# Mux_side_B.net
KiCad netlist of a schematic drawn in Altium Designer
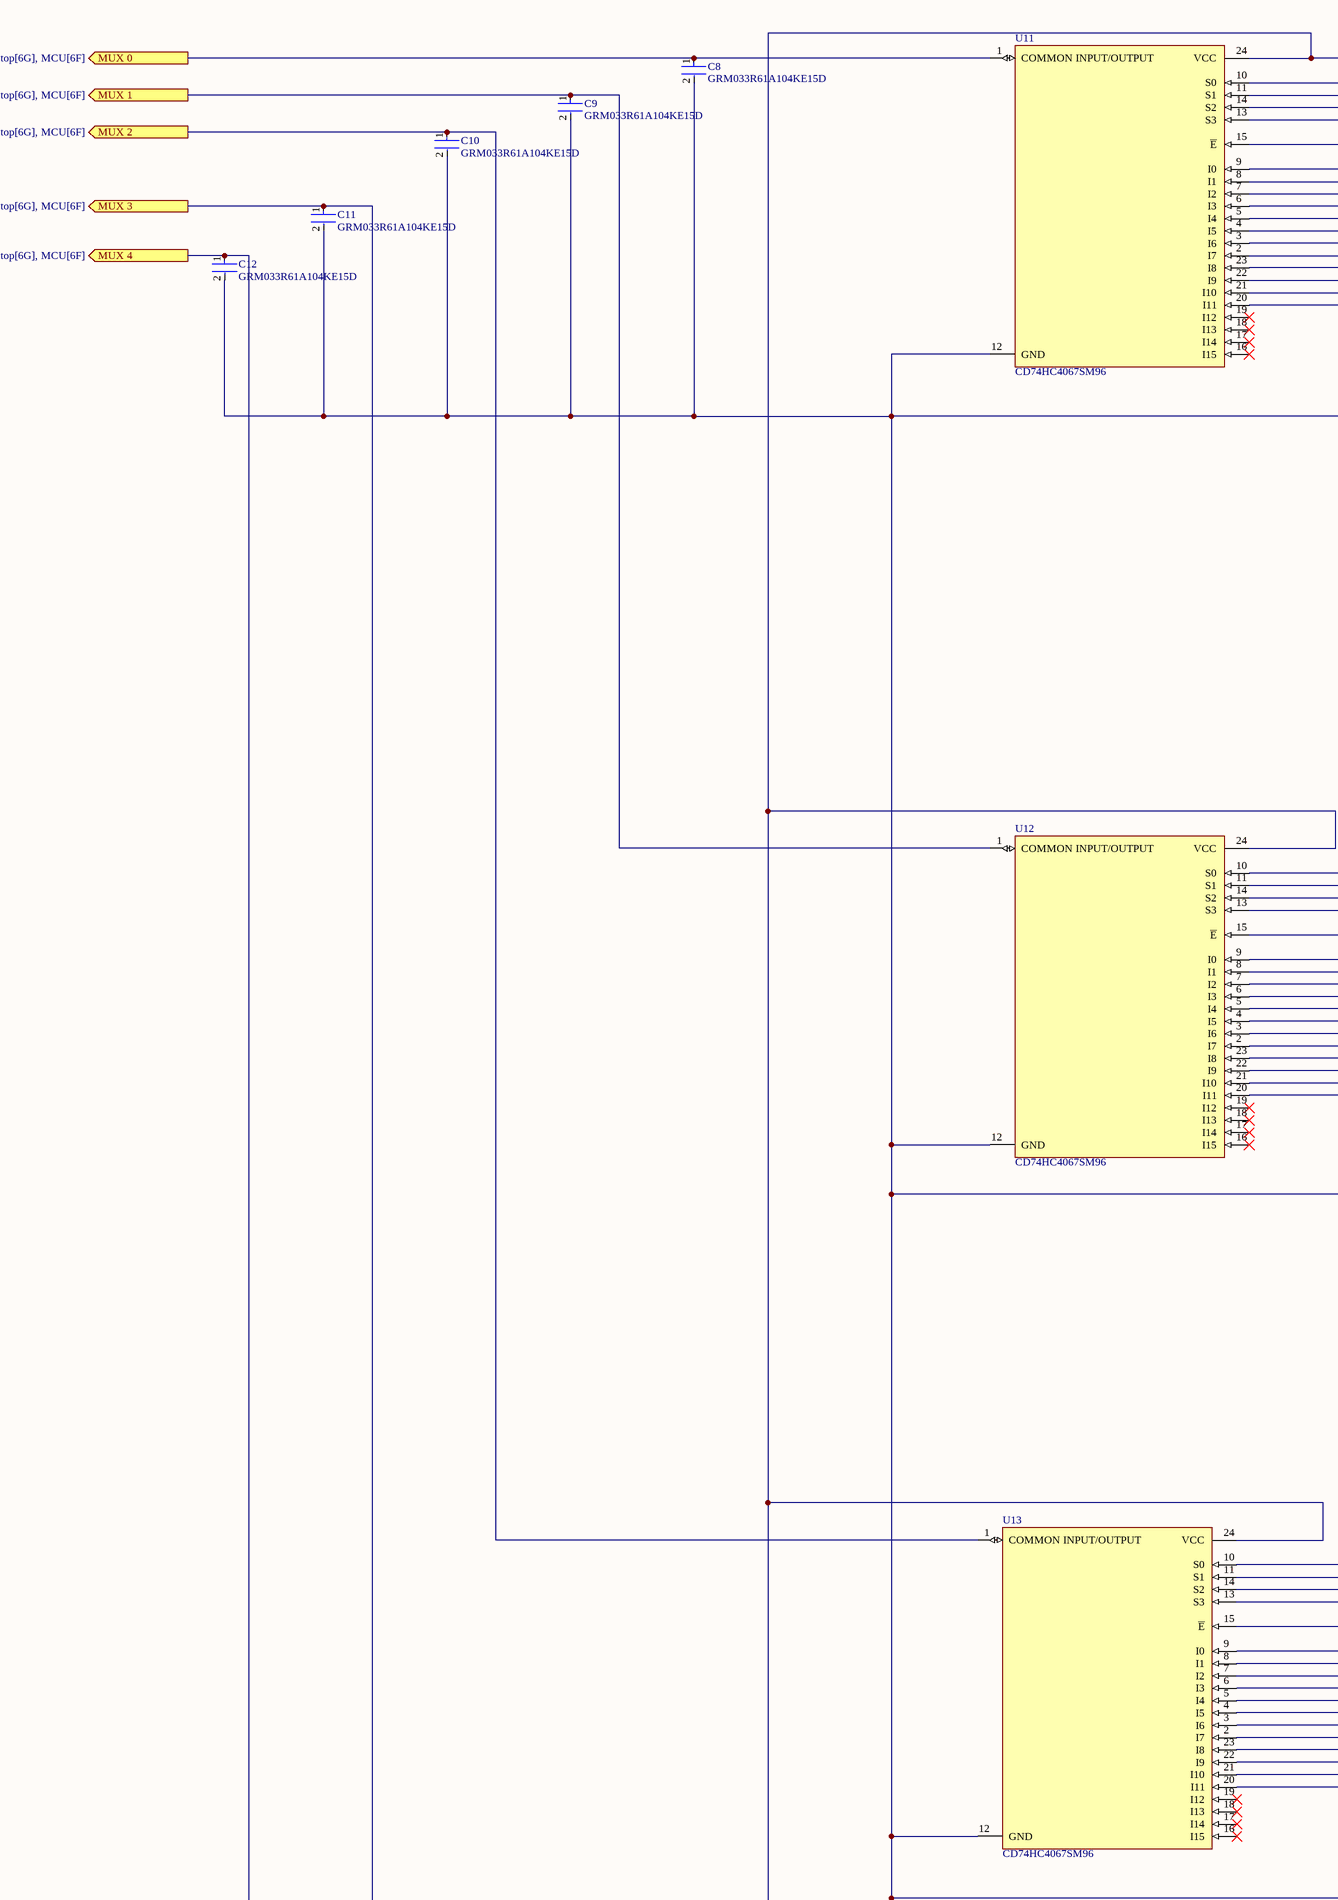
[diagram p0: Mux side B (5-8).SchDoc, top left]
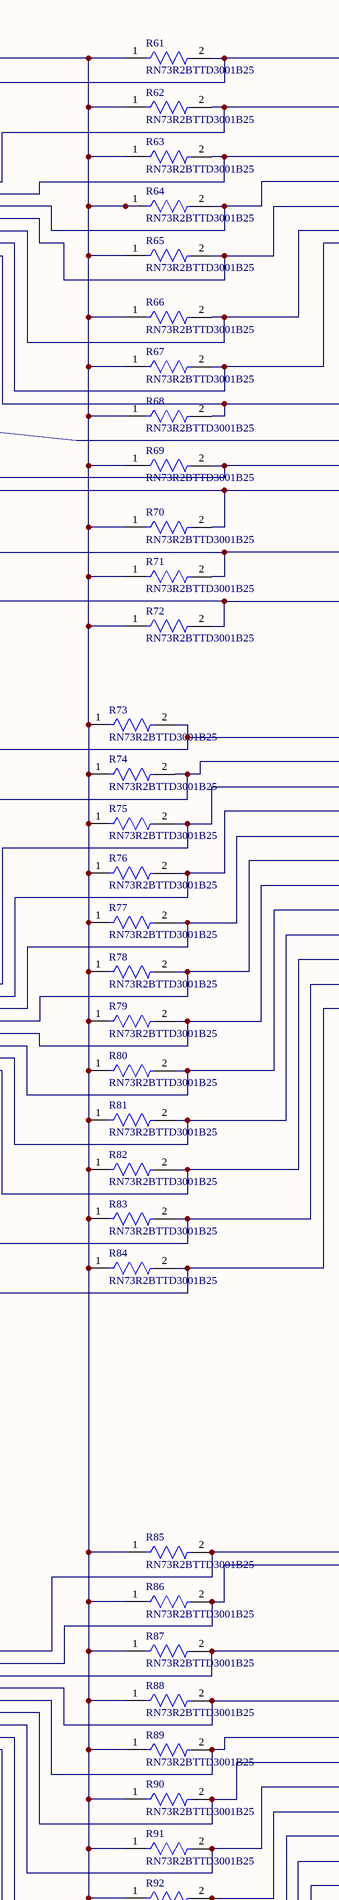
[diagram p1: Mux side B (5-8).SchDoc, top middle]
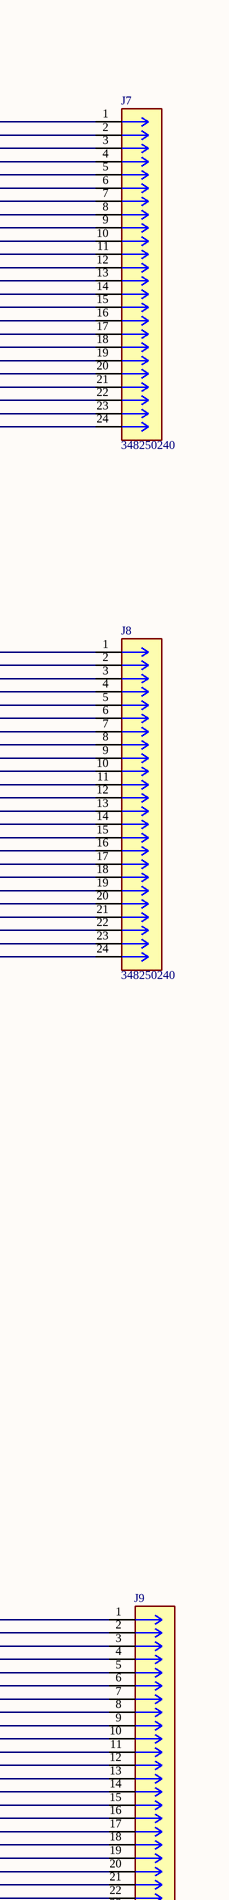
[diagram p2: Mux side B (5-8).SchDoc, top right]
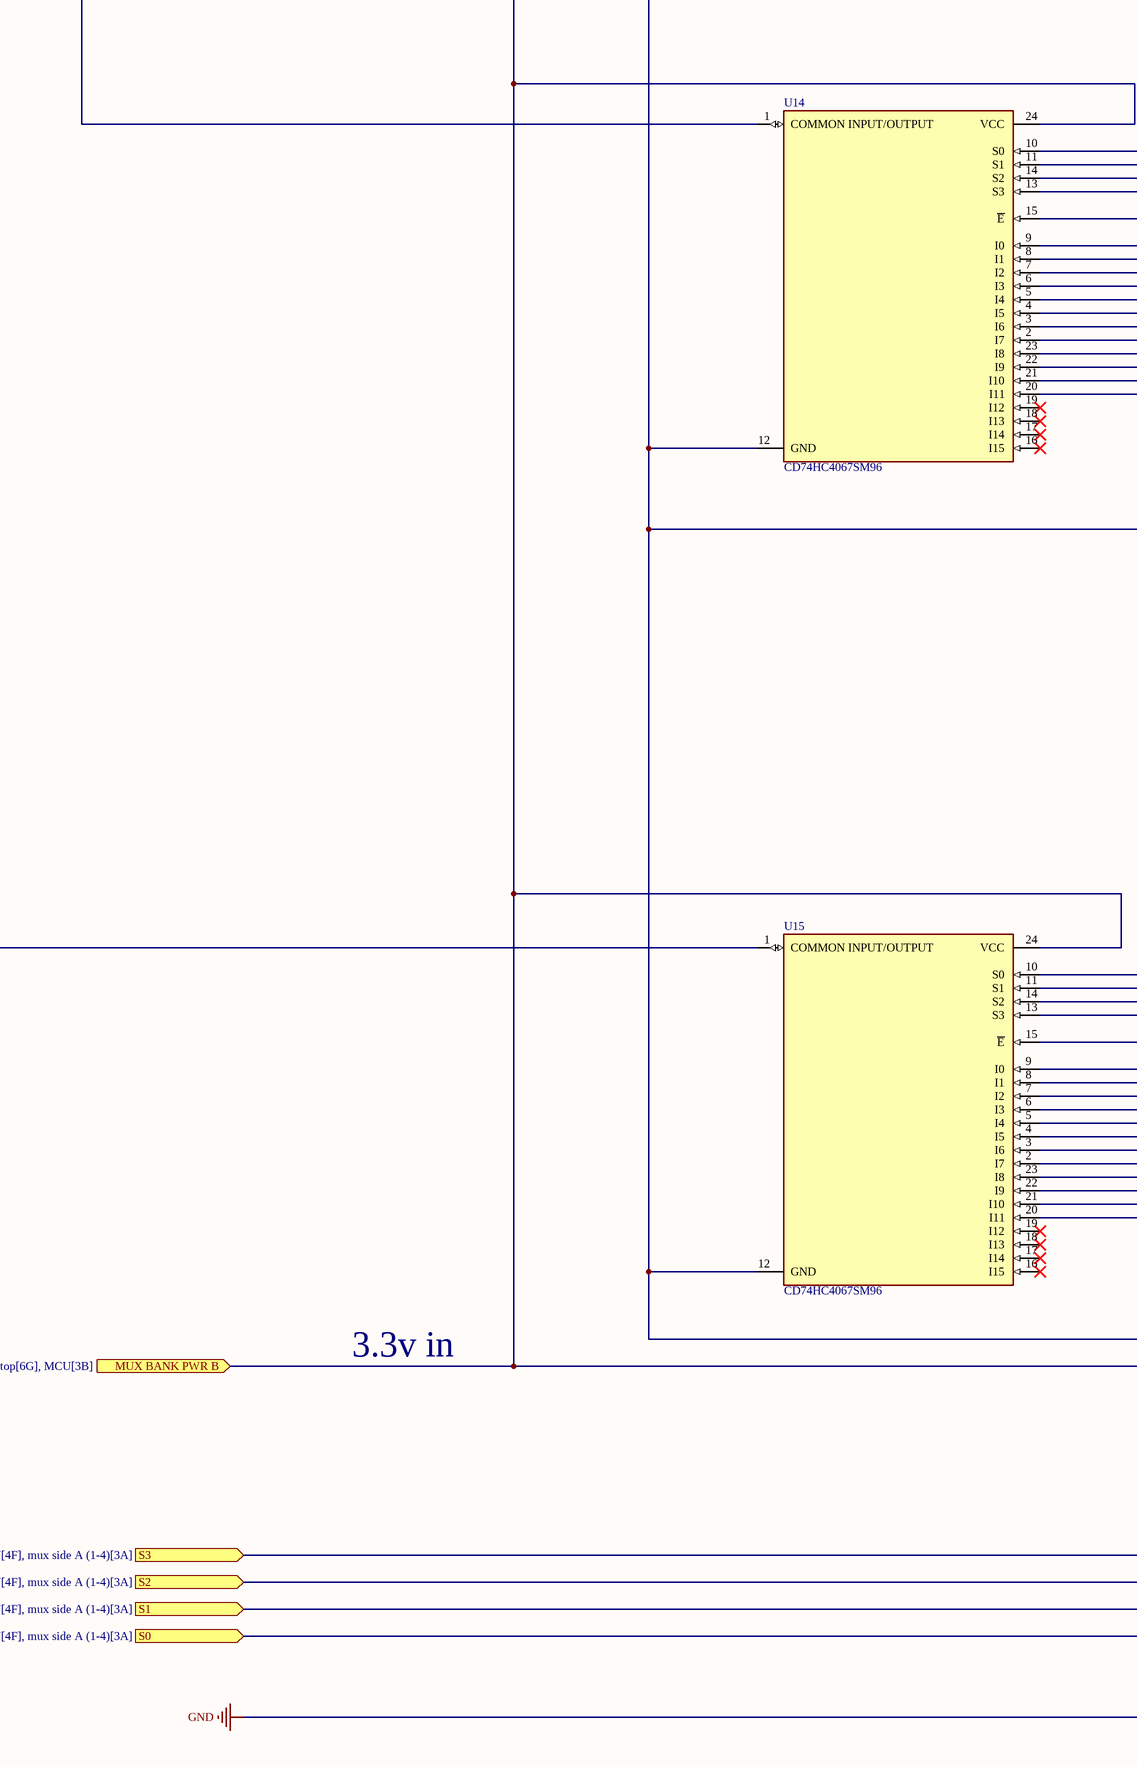
[diagram p3: Mux side B (5-8).SchDoc, bottom left]
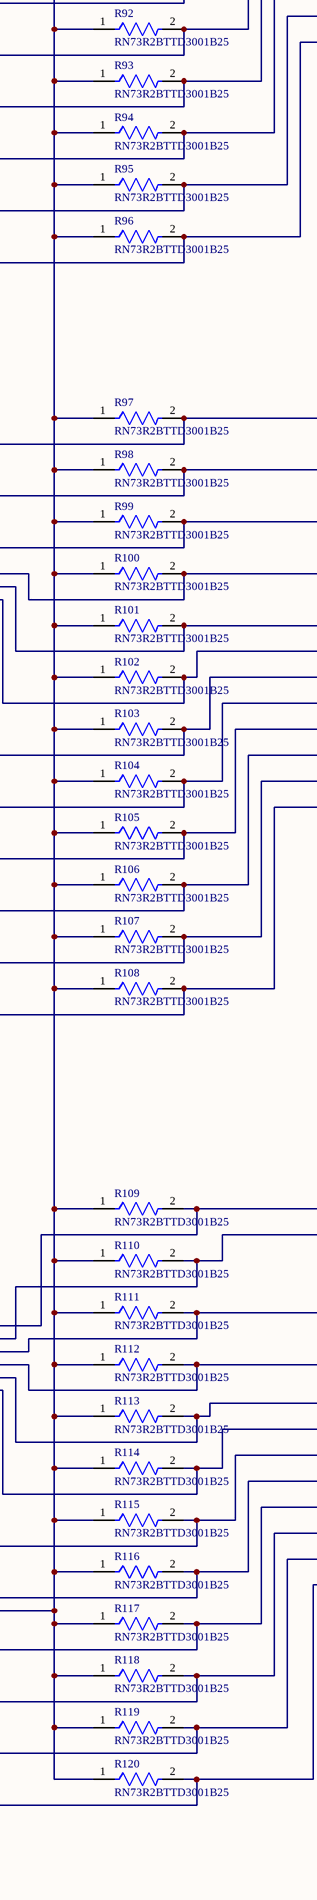
[diagram p4: Mux side B (5-8).SchDoc, bottom middle]
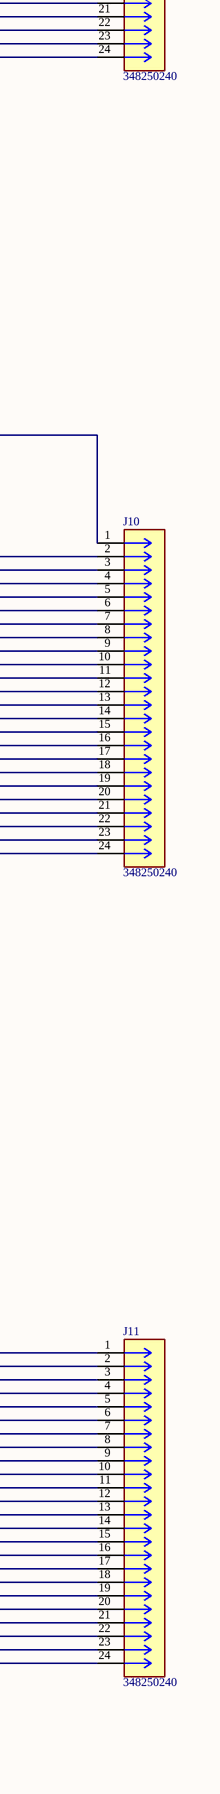
[diagram p5: Mux side B (5-8).SchDoc, bottom right]

(export (version "E")
  (design (tool "Eeschema 10.0.6"))
  (components
    (comp (ref "C8")
      (value "GRM033R61A104KE15D")
      (footprint "FP-GRM033-0_03-IPC_C")
      (description "Chip Multilayer Ceramic Capacitors for General Purpose, 0201, 0.10uF, X5R, 15%, 10%, 10V")
      (fields (field (name "TOLERANCE") "10%") (field (name "VOLTAGE") "10V"))
      (libsource (lib "Altium Content Vault") (part "b4654b650e69147ec39a6b967a45e02"))
    )
    (comp (ref "C9")
      (value "GRM033R61A104KE15D")
      (footprint "FP-GRM033-0_03-IPC_C")
      (description "Chip Multilayer Ceramic Capacitors for General Purpose, 0201, 0.10uF, X5R, 15%, 10%, 10V")
      (fields (field (name "TOLERANCE") "10%") (field (name "VOLTAGE") "10V"))
      (libsource (lib "Altium Content Vault") (part "b4654b650e69147ec39a6b967a45e02"))
    )
    (comp (ref "C10")
      (value "GRM033R61A104KE15D")
      (footprint "FP-GRM033-0_03-IPC_C")
      (description "Chip Multilayer Ceramic Capacitors for General Purpose, 0201, 0.10uF, X5R, 15%, 10%, 10V")
      (fields (field (name "TOLERANCE") "10%") (field (name "VOLTAGE") "10V"))
      (libsource (lib "Altium Content Vault") (part "b4654b650e69147ec39a6b967a45e02"))
    )
    (comp (ref "C11")
      (value "GRM033R61A104KE15D")
      (footprint "FP-GRM033-0_03-IPC_C")
      (description "Chip Multilayer Ceramic Capacitors for General Purpose, 0201, 0.10uF, X5R, 15%, 10%, 10V")
      (fields (field (name "TOLERANCE") "10%") (field (name "VOLTAGE") "10V"))
      (libsource (lib "Altium Content Vault") (part "b4654b650e69147ec39a6b967a45e02"))
    )
    (comp (ref "C12")
      (value "GRM033R61A104KE15D")
      (footprint "FP-GRM033-0_03-IPC_C")
      (description "Chip Multilayer Ceramic Capacitors for General Purpose, 0201, 0.10uF, X5R, 15%, 10%, 10V")
      (fields (field (name "TOLERANCE") "10%") (field (name "VOLTAGE") "10V"))
      (libsource (lib "Altium Content Vault") (part "b4654b650e69147ec39a6b967a45e02"))
    )
    (comp (ref "J7")
      (value "348250240")
      (footprint "CONN_SD-34825-001_24_MOL")
      (libsource (lib "348250240") (part "348250240"))
    )
    (comp (ref "J8")
      (value "348250240")
      (footprint "CONN_SD-34825-001_24_MOL")
      (libsource (lib "348250240") (part "348250240"))
    )
    (comp (ref "J9")
      (value "348250240")
      (footprint "CONN_SD-34825-001_24_MOL")
      (libsource (lib "348250240") (part "348250240"))
    )
    (comp (ref "J10")
      (value "348250240")
      (footprint "CONN_SD-34825-001_24_MOL")
      (libsource (lib "348250240") (part "348250240"))
    )
    (comp (ref "J11")
      (value "348250240")
      (footprint "CONN_SD-34825-001_24_MOL")
      (libsource (lib "348250240") (part "348250240"))
    )
    (comp (ref "R61")
      (value "RN73R2BTTD3001B25")
      (footprint "FP-RN73R2B-IPC_A")
      (description "3kΩ ±0.1% 0.25W, 1/4W Chip Resistor 1206 (3216 Metric) Moisture Resistant Thin Film")
      (libsource (lib "Altium Content Vault") (part "1029c3af85768c4190bb7ad29bc67b5"))
    )
    (comp (ref "R62")
      (value "RN73R2BTTD3001B25")
      (footprint "FP-RN73R2B-IPC_A")
      (description "3kΩ ±0.1% 0.25W, 1/4W Chip Resistor 1206 (3216 Metric) Moisture Resistant Thin Film")
      (libsource (lib "Altium Content Vault") (part "1029c3af85768c4190bb7ad29bc67b5"))
    )
    (comp (ref "R63")
      (value "RN73R2BTTD3001B25")
      (footprint "FP-RN73R2B-IPC_A")
      (description "3kΩ ±0.1% 0.25W, 1/4W Chip Resistor 1206 (3216 Metric) Moisture Resistant Thin Film")
      (libsource (lib "Altium Content Vault") (part "1029c3af85768c4190bb7ad29bc67b5"))
    )
    (comp (ref "R64")
      (value "RN73R2BTTD3001B25")
      (footprint "FP-RN73R2B-IPC_A")
      (description "3kΩ ±0.1% 0.25W, 1/4W Chip Resistor 1206 (3216 Metric) Moisture Resistant Thin Film")
      (libsource (lib "Altium Content Vault") (part "1029c3af85768c4190bb7ad29bc67b5"))
    )
    (comp (ref "R65")
      (value "RN73R2BTTD3001B25")
      (footprint "FP-RN73R2B-IPC_A")
      (description "3kΩ ±0.1% 0.25W, 1/4W Chip Resistor 1206 (3216 Metric) Moisture Resistant Thin Film")
      (libsource (lib "Altium Content Vault") (part "1029c3af85768c4190bb7ad29bc67b5"))
    )
    (comp (ref "R66")
      (value "RN73R2BTTD3001B25")
      (footprint "FP-RN73R2B-IPC_A")
      (description "3kΩ ±0.1% 0.25W, 1/4W Chip Resistor 1206 (3216 Metric) Moisture Resistant Thin Film")
      (libsource (lib "Altium Content Vault") (part "1029c3af85768c4190bb7ad29bc67b5"))
    )
    (comp (ref "R67")
      (value "RN73R2BTTD3001B25")
      (footprint "FP-RN73R2B-IPC_A")
      (description "3kΩ ±0.1% 0.25W, 1/4W Chip Resistor 1206 (3216 Metric) Moisture Resistant Thin Film")
      (libsource (lib "Altium Content Vault") (part "1029c3af85768c4190bb7ad29bc67b5"))
    )
    (comp (ref "R68")
      (value "RN73R2BTTD3001B25")
      (footprint "FP-RN73R2B-IPC_A")
      (description "3kΩ ±0.1% 0.25W, 1/4W Chip Resistor 1206 (3216 Metric) Moisture Resistant Thin Film")
      (libsource (lib "Altium Content Vault") (part "1029c3af85768c4190bb7ad29bc67b5"))
    )
    (comp (ref "R69")
      (value "RN73R2BTTD3001B25")
      (footprint "FP-RN73R2B-IPC_A")
      (description "3kΩ ±0.1% 0.25W, 1/4W Chip Resistor 1206 (3216 Metric) Moisture Resistant Thin Film")
      (libsource (lib "Altium Content Vault") (part "1029c3af85768c4190bb7ad29bc67b5"))
    )
    (comp (ref "R70")
      (value "RN73R2BTTD3001B25")
      (footprint "FP-RN73R2B-IPC_A")
      (description "3kΩ ±0.1% 0.25W, 1/4W Chip Resistor 1206 (3216 Metric) Moisture Resistant Thin Film")
      (libsource (lib "Altium Content Vault") (part "1029c3af85768c4190bb7ad29bc67b5"))
    )
    (comp (ref "R71")
      (value "RN73R2BTTD3001B25")
      (footprint "FP-RN73R2B-IPC_A")
      (description "3kΩ ±0.1% 0.25W, 1/4W Chip Resistor 1206 (3216 Metric) Moisture Resistant Thin Film")
      (libsource (lib "Altium Content Vault") (part "1029c3af85768c4190bb7ad29bc67b5"))
    )
    (comp (ref "R72")
      (value "RN73R2BTTD3001B25")
      (footprint "FP-RN73R2B-IPC_A")
      (description "3kΩ ±0.1% 0.25W, 1/4W Chip Resistor 1206 (3216 Metric) Moisture Resistant Thin Film")
      (libsource (lib "Altium Content Vault") (part "1029c3af85768c4190bb7ad29bc67b5"))
    )
    (comp (ref "R73")
      (value "RN73R2BTTD3001B25")
      (footprint "FP-RN73R2B-IPC_A")
      (description "3kΩ ±0.1% 0.25W, 1/4W Chip Resistor 1206 (3216 Metric) Moisture Resistant Thin Film")
      (libsource (lib "Altium Content Vault") (part "1029c3af85768c4190bb7ad29bc67b5"))
    )
    (comp (ref "R74")
      (value "RN73R2BTTD3001B25")
      (footprint "FP-RN73R2B-IPC_A")
      (description "3kΩ ±0.1% 0.25W, 1/4W Chip Resistor 1206 (3216 Metric) Moisture Resistant Thin Film")
      (libsource (lib "Altium Content Vault") (part "1029c3af85768c4190bb7ad29bc67b5"))
    )
    (comp (ref "R75")
      (value "RN73R2BTTD3001B25")
      (footprint "FP-RN73R2B-IPC_A")
      (description "3kΩ ±0.1% 0.25W, 1/4W Chip Resistor 1206 (3216 Metric) Moisture Resistant Thin Film")
      (libsource (lib "Altium Content Vault") (part "1029c3af85768c4190bb7ad29bc67b5"))
    )
    (comp (ref "R76")
      (value "RN73R2BTTD3001B25")
      (footprint "FP-RN73R2B-IPC_A")
      (description "3kΩ ±0.1% 0.25W, 1/4W Chip Resistor 1206 (3216 Metric) Moisture Resistant Thin Film")
      (libsource (lib "Altium Content Vault") (part "1029c3af85768c4190bb7ad29bc67b5"))
    )
    (comp (ref "R77")
      (value "RN73R2BTTD3001B25")
      (footprint "FP-RN73R2B-IPC_A")
      (description "3kΩ ±0.1% 0.25W, 1/4W Chip Resistor 1206 (3216 Metric) Moisture Resistant Thin Film")
      (libsource (lib "Altium Content Vault") (part "1029c3af85768c4190bb7ad29bc67b5"))
    )
    (comp (ref "R78")
      (value "RN73R2BTTD3001B25")
      (footprint "FP-RN73R2B-IPC_A")
      (description "3kΩ ±0.1% 0.25W, 1/4W Chip Resistor 1206 (3216 Metric) Moisture Resistant Thin Film")
      (libsource (lib "Altium Content Vault") (part "1029c3af85768c4190bb7ad29bc67b5"))
    )
    (comp (ref "R79")
      (value "RN73R2BTTD3001B25")
      (footprint "FP-RN73R2B-IPC_A")
      (description "3kΩ ±0.1% 0.25W, 1/4W Chip Resistor 1206 (3216 Metric) Moisture Resistant Thin Film")
      (libsource (lib "Altium Content Vault") (part "1029c3af85768c4190bb7ad29bc67b5"))
    )
    (comp (ref "R80")
      (value "RN73R2BTTD3001B25")
      (footprint "FP-RN73R2B-IPC_A")
      (description "3kΩ ±0.1% 0.25W, 1/4W Chip Resistor 1206 (3216 Metric) Moisture Resistant Thin Film")
      (libsource (lib "Altium Content Vault") (part "1029c3af85768c4190bb7ad29bc67b5"))
    )
    (comp (ref "R81")
      (value "RN73R2BTTD3001B25")
      (footprint "FP-RN73R2B-IPC_A")
      (description "3kΩ ±0.1% 0.25W, 1/4W Chip Resistor 1206 (3216 Metric) Moisture Resistant Thin Film")
      (libsource (lib "Altium Content Vault") (part "1029c3af85768c4190bb7ad29bc67b5"))
    )
    (comp (ref "R82")
      (value "RN73R2BTTD3001B25")
      (footprint "FP-RN73R2B-IPC_A")
      (description "3kΩ ±0.1% 0.25W, 1/4W Chip Resistor 1206 (3216 Metric) Moisture Resistant Thin Film")
      (libsource (lib "Altium Content Vault") (part "1029c3af85768c4190bb7ad29bc67b5"))
    )
    (comp (ref "R83")
      (value "RN73R2BTTD3001B25")
      (footprint "FP-RN73R2B-IPC_A")
      (description "3kΩ ±0.1% 0.25W, 1/4W Chip Resistor 1206 (3216 Metric) Moisture Resistant Thin Film")
      (libsource (lib "Altium Content Vault") (part "1029c3af85768c4190bb7ad29bc67b5"))
    )
    (comp (ref "R84")
      (value "RN73R2BTTD3001B25")
      (footprint "FP-RN73R2B-IPC_A")
      (description "3kΩ ±0.1% 0.25W, 1/4W Chip Resistor 1206 (3216 Metric) Moisture Resistant Thin Film")
      (libsource (lib "Altium Content Vault") (part "1029c3af85768c4190bb7ad29bc67b5"))
    )
    (comp (ref "R85")
      (value "RN73R2BTTD3001B25")
      (footprint "FP-RN73R2B-IPC_A")
      (description "3kΩ ±0.1% 0.25W, 1/4W Chip Resistor 1206 (3216 Metric) Moisture Resistant Thin Film")
      (libsource (lib "Altium Content Vault") (part "1029c3af85768c4190bb7ad29bc67b5"))
    )
    (comp (ref "R86")
      (value "RN73R2BTTD3001B25")
      (footprint "FP-RN73R2B-IPC_A")
      (description "3kΩ ±0.1% 0.25W, 1/4W Chip Resistor 1206 (3216 Metric) Moisture Resistant Thin Film")
      (libsource (lib "Altium Content Vault") (part "1029c3af85768c4190bb7ad29bc67b5"))
    )
    (comp (ref "R87")
      (value "RN73R2BTTD3001B25")
      (footprint "FP-RN73R2B-IPC_A")
      (description "3kΩ ±0.1% 0.25W, 1/4W Chip Resistor 1206 (3216 Metric) Moisture Resistant Thin Film")
      (libsource (lib "Altium Content Vault") (part "1029c3af85768c4190bb7ad29bc67b5"))
    )
    (comp (ref "R88")
      (value "RN73R2BTTD3001B25")
      (footprint "FP-RN73R2B-IPC_A")
      (description "3kΩ ±0.1% 0.25W, 1/4W Chip Resistor 1206 (3216 Metric) Moisture Resistant Thin Film")
      (libsource (lib "Altium Content Vault") (part "1029c3af85768c4190bb7ad29bc67b5"))
    )
    (comp (ref "R89")
      (value "RN73R2BTTD3001B25")
      (footprint "FP-RN73R2B-IPC_A")
      (description "3kΩ ±0.1% 0.25W, 1/4W Chip Resistor 1206 (3216 Metric) Moisture Resistant Thin Film")
      (libsource (lib "Altium Content Vault") (part "1029c3af85768c4190bb7ad29bc67b5"))
    )
    (comp (ref "R90")
      (value "RN73R2BTTD3001B25")
      (footprint "FP-RN73R2B-IPC_A")
      (description "3kΩ ±0.1% 0.25W, 1/4W Chip Resistor 1206 (3216 Metric) Moisture Resistant Thin Film")
      (libsource (lib "Altium Content Vault") (part "1029c3af85768c4190bb7ad29bc67b5"))
    )
    (comp (ref "R91")
      (value "RN73R2BTTD3001B25")
      (footprint "FP-RN73R2B-IPC_A")
      (description "3kΩ ±0.1% 0.25W, 1/4W Chip Resistor 1206 (3216 Metric) Moisture Resistant Thin Film")
      (libsource (lib "Altium Content Vault") (part "1029c3af85768c4190bb7ad29bc67b5"))
    )
    (comp (ref "R92")
      (value "RN73R2BTTD3001B25")
      (footprint "FP-RN73R2B-IPC_A")
      (description "3kΩ ±0.1% 0.25W, 1/4W Chip Resistor 1206 (3216 Metric) Moisture Resistant Thin Film")
      (libsource (lib "Altium Content Vault") (part "1029c3af85768c4190bb7ad29bc67b5"))
    )
    (comp (ref "R93")
      (value "RN73R2BTTD3001B25")
      (footprint "FP-RN73R2B-IPC_A")
      (description "3kΩ ±0.1% 0.25W, 1/4W Chip Resistor 1206 (3216 Metric) Moisture Resistant Thin Film")
      (libsource (lib "Altium Content Vault") (part "1029c3af85768c4190bb7ad29bc67b5"))
    )
    (comp (ref "R94")
      (value "RN73R2BTTD3001B25")
      (footprint "FP-RN73R2B-IPC_A")
      (description "3kΩ ±0.1% 0.25W, 1/4W Chip Resistor 1206 (3216 Metric) Moisture Resistant Thin Film")
      (libsource (lib "Altium Content Vault") (part "1029c3af85768c4190bb7ad29bc67b5"))
    )
    (comp (ref "R95")
      (value "RN73R2BTTD3001B25")
      (footprint "FP-RN73R2B-IPC_A")
      (description "3kΩ ±0.1% 0.25W, 1/4W Chip Resistor 1206 (3216 Metric) Moisture Resistant Thin Film")
      (libsource (lib "Altium Content Vault") (part "1029c3af85768c4190bb7ad29bc67b5"))
    )
    (comp (ref "R96")
      (value "RN73R2BTTD3001B25")
      (footprint "FP-RN73R2B-IPC_A")
      (description "3kΩ ±0.1% 0.25W, 1/4W Chip Resistor 1206 (3216 Metric) Moisture Resistant Thin Film")
      (libsource (lib "Altium Content Vault") (part "1029c3af85768c4190bb7ad29bc67b5"))
    )
    (comp (ref "R97")
      (value "RN73R2BTTD3001B25")
      (footprint "FP-RN73R2B-IPC_A")
      (description "3kΩ ±0.1% 0.25W, 1/4W Chip Resistor 1206 (3216 Metric) Moisture Resistant Thin Film")
      (libsource (lib "Altium Content Vault") (part "1029c3af85768c4190bb7ad29bc67b5"))
    )
    (comp (ref "R98")
      (value "RN73R2BTTD3001B25")
      (footprint "FP-RN73R2B-IPC_A")
      (description "3kΩ ±0.1% 0.25W, 1/4W Chip Resistor 1206 (3216 Metric) Moisture Resistant Thin Film")
      (libsource (lib "Altium Content Vault") (part "1029c3af85768c4190bb7ad29bc67b5"))
    )
    (comp (ref "R99")
      (value "RN73R2BTTD3001B25")
      (footprint "FP-RN73R2B-IPC_A")
      (description "3kΩ ±0.1% 0.25W, 1/4W Chip Resistor 1206 (3216 Metric) Moisture Resistant Thin Film")
      (libsource (lib "Altium Content Vault") (part "1029c3af85768c4190bb7ad29bc67b5"))
    )
    (comp (ref "R100")
      (value "RN73R2BTTD3001B25")
      (footprint "FP-RN73R2B-IPC_A")
      (description "3kΩ ±0.1% 0.25W, 1/4W Chip Resistor 1206 (3216 Metric) Moisture Resistant Thin Film")
      (libsource (lib "Altium Content Vault") (part "1029c3af85768c4190bb7ad29bc67b5"))
    )
    (comp (ref "R101")
      (value "RN73R2BTTD3001B25")
      (footprint "FP-RN73R2B-IPC_A")
      (description "3kΩ ±0.1% 0.25W, 1/4W Chip Resistor 1206 (3216 Metric) Moisture Resistant Thin Film")
      (libsource (lib "Altium Content Vault") (part "1029c3af85768c4190bb7ad29bc67b5"))
    )
    (comp (ref "R102")
      (value "RN73R2BTTD3001B25")
      (footprint "FP-RN73R2B-IPC_A")
      (description "3kΩ ±0.1% 0.25W, 1/4W Chip Resistor 1206 (3216 Metric) Moisture Resistant Thin Film")
      (libsource (lib "Altium Content Vault") (part "1029c3af85768c4190bb7ad29bc67b5"))
    )
    (comp (ref "R103")
      (value "RN73R2BTTD3001B25")
      (footprint "FP-RN73R2B-IPC_A")
      (description "3kΩ ±0.1% 0.25W, 1/4W Chip Resistor 1206 (3216 Metric) Moisture Resistant Thin Film")
      (libsource (lib "Altium Content Vault") (part "1029c3af85768c4190bb7ad29bc67b5"))
    )
    (comp (ref "R104")
      (value "RN73R2BTTD3001B25")
      (footprint "FP-RN73R2B-IPC_A")
      (description "3kΩ ±0.1% 0.25W, 1/4W Chip Resistor 1206 (3216 Metric) Moisture Resistant Thin Film")
      (libsource (lib "Altium Content Vault") (part "1029c3af85768c4190bb7ad29bc67b5"))
    )
    (comp (ref "R105")
      (value "RN73R2BTTD3001B25")
      (footprint "FP-RN73R2B-IPC_A")
      (description "3kΩ ±0.1% 0.25W, 1/4W Chip Resistor 1206 (3216 Metric) Moisture Resistant Thin Film")
      (libsource (lib "Altium Content Vault") (part "1029c3af85768c4190bb7ad29bc67b5"))
    )
    (comp (ref "R106")
      (value "RN73R2BTTD3001B25")
      (footprint "FP-RN73R2B-IPC_A")
      (description "3kΩ ±0.1% 0.25W, 1/4W Chip Resistor 1206 (3216 Metric) Moisture Resistant Thin Film")
      (libsource (lib "Altium Content Vault") (part "1029c3af85768c4190bb7ad29bc67b5"))
    )
    (comp (ref "R107")
      (value "RN73R2BTTD3001B25")
      (footprint "FP-RN73R2B-IPC_A")
      (description "3kΩ ±0.1% 0.25W, 1/4W Chip Resistor 1206 (3216 Metric) Moisture Resistant Thin Film")
      (libsource (lib "Altium Content Vault") (part "1029c3af85768c4190bb7ad29bc67b5"))
    )
    (comp (ref "R108")
      (value "RN73R2BTTD3001B25")
      (footprint "FP-RN73R2B-IPC_A")
      (description "3kΩ ±0.1% 0.25W, 1/4W Chip Resistor 1206 (3216 Metric) Moisture Resistant Thin Film")
      (libsource (lib "Altium Content Vault") (part "1029c3af85768c4190bb7ad29bc67b5"))
    )
    (comp (ref "R109")
      (value "RN73R2BTTD3001B25")
      (footprint "FP-RN73R2B-IPC_A")
      (description "3kΩ ±0.1% 0.25W, 1/4W Chip Resistor 1206 (3216 Metric) Moisture Resistant Thin Film")
      (libsource (lib "Altium Content Vault") (part "1029c3af85768c4190bb7ad29bc67b5"))
    )
    (comp (ref "R110")
      (value "RN73R2BTTD3001B25")
      (footprint "FP-RN73R2B-IPC_A")
      (description "3kΩ ±0.1% 0.25W, 1/4W Chip Resistor 1206 (3216 Metric) Moisture Resistant Thin Film")
      (libsource (lib "Altium Content Vault") (part "1029c3af85768c4190bb7ad29bc67b5"))
    )
    (comp (ref "R111")
      (value "RN73R2BTTD3001B25")
      (footprint "FP-RN73R2B-IPC_A")
      (description "3kΩ ±0.1% 0.25W, 1/4W Chip Resistor 1206 (3216 Metric) Moisture Resistant Thin Film")
      (libsource (lib "Altium Content Vault") (part "1029c3af85768c4190bb7ad29bc67b5"))
    )
    (comp (ref "R112")
      (value "RN73R2BTTD3001B25")
      (footprint "FP-RN73R2B-IPC_A")
      (description "3kΩ ±0.1% 0.25W, 1/4W Chip Resistor 1206 (3216 Metric) Moisture Resistant Thin Film")
      (libsource (lib "Altium Content Vault") (part "1029c3af85768c4190bb7ad29bc67b5"))
    )
    (comp (ref "R113")
      (value "RN73R2BTTD3001B25")
      (footprint "FP-RN73R2B-IPC_A")
      (description "3kΩ ±0.1% 0.25W, 1/4W Chip Resistor 1206 (3216 Metric) Moisture Resistant Thin Film")
      (libsource (lib "Altium Content Vault") (part "1029c3af85768c4190bb7ad29bc67b5"))
    )
    (comp (ref "R114")
      (value "RN73R2BTTD3001B25")
      (footprint "FP-RN73R2B-IPC_A")
      (description "3kΩ ±0.1% 0.25W, 1/4W Chip Resistor 1206 (3216 Metric) Moisture Resistant Thin Film")
      (libsource (lib "Altium Content Vault") (part "1029c3af85768c4190bb7ad29bc67b5"))
    )
    (comp (ref "R115")
      (value "RN73R2BTTD3001B25")
      (footprint "FP-RN73R2B-IPC_A")
      (description "3kΩ ±0.1% 0.25W, 1/4W Chip Resistor 1206 (3216 Metric) Moisture Resistant Thin Film")
      (libsource (lib "Altium Content Vault") (part "1029c3af85768c4190bb7ad29bc67b5"))
    )
    (comp (ref "R116")
      (value "RN73R2BTTD3001B25")
      (footprint "FP-RN73R2B-IPC_A")
      (description "3kΩ ±0.1% 0.25W, 1/4W Chip Resistor 1206 (3216 Metric) Moisture Resistant Thin Film")
      (libsource (lib "Altium Content Vault") (part "1029c3af85768c4190bb7ad29bc67b5"))
    )
    (comp (ref "R117")
      (value "RN73R2BTTD3001B25")
      (footprint "FP-RN73R2B-IPC_A")
      (description "3kΩ ±0.1% 0.25W, 1/4W Chip Resistor 1206 (3216 Metric) Moisture Resistant Thin Film")
      (libsource (lib "Altium Content Vault") (part "1029c3af85768c4190bb7ad29bc67b5"))
    )
    (comp (ref "R118")
      (value "RN73R2BTTD3001B25")
      (footprint "FP-RN73R2B-IPC_A")
      (description "3kΩ ±0.1% 0.25W, 1/4W Chip Resistor 1206 (3216 Metric) Moisture Resistant Thin Film")
      (libsource (lib "Altium Content Vault") (part "1029c3af85768c4190bb7ad29bc67b5"))
    )
    (comp (ref "R119")
      (value "RN73R2BTTD3001B25")
      (footprint "FP-RN73R2B-IPC_A")
      (description "3kΩ ±0.1% 0.25W, 1/4W Chip Resistor 1206 (3216 Metric) Moisture Resistant Thin Film")
      (libsource (lib "Altium Content Vault") (part "1029c3af85768c4190bb7ad29bc67b5"))
    )
    (comp (ref "R120")
      (value "RN73R2BTTD3001B25")
      (footprint "FP-RN73R2B-IPC_A")
      (description "3kΩ ±0.1% 0.25W, 1/4W Chip Resistor 1206 (3216 Metric) Moisture Resistant Thin Film")
      (libsource (lib "Altium Content Vault") (part "1029c3af85768c4190bb7ad29bc67b5"))
    )
    (comp (ref "U11")
      (value "CD74HC4067SM96")
      (footprint "FP-DB0024A-IPC_C")
      (description "IC MUX/DEMUX 1X16 24SSOP")
      (libsource (lib "Altium Content Vault") (part "3c03c7c8a240a5fb11098c607706683"))
    )
    (comp (ref "U12")
      (value "CD74HC4067SM96")
      (footprint "FP-DB0024A-IPC_C")
      (description "IC MUX/DEMUX 1X16 24SSOP")
      (libsource (lib "Altium Content Vault") (part "3c03c7c8a240a5fb11098c607706683"))
    )
    (comp (ref "U13")
      (value "CD74HC4067SM96")
      (footprint "FP-DB0024A-IPC_C")
      (description "IC MUX/DEMUX 1X16 24SSOP")
      (libsource (lib "Altium Content Vault") (part "3c03c7c8a240a5fb11098c607706683"))
    )
    (comp (ref "U14")
      (value "CD74HC4067SM96")
      (footprint "FP-DB0024A-IPC_C")
      (description "IC MUX/DEMUX 1X16 24SSOP")
      (libsource (lib "Altium Content Vault") (part "3c03c7c8a240a5fb11098c607706683"))
    )
    (comp (ref "U15")
      (value "CD74HC4067SM96")
      (footprint "FP-DB0024A-IPC_C")
      (description "IC MUX/DEMUX 1X16 24SSOP")
      (libsource (lib "Altium Content Vault") (part "3c03c7c8a240a5fb11098c607706683"))
    )
  )
  (nets
    (net (code "1") (name "/MUX 0") (class "Default")
      (node (ref "C8") (pin "1") (pinfunction "1_1") (pintype "passive"))
      (node (ref "U11") (pin "1") (pinfunction "COMMON_INPUT/OUTPUT_1") (pintype "bidirectional"))
    )
    (net (code "2") (name "/MUX 1") (class "Default")
      (node (ref "C9") (pin "1") (pinfunction "1_1") (pintype "passive"))
      (node (ref "U12") (pin "1") (pinfunction "COMMON_INPUT/OUTPUT_1") (pintype "bidirectional"))
    )
    (net (code "3") (name "/MUX 2") (class "Default")
      (node (ref "C10") (pin "1") (pinfunction "1_1") (pintype "passive"))
      (node (ref "U13") (pin "1") (pinfunction "COMMON_INPUT/OUTPUT_1") (pintype "bidirectional"))
    )
    (net (code "4") (name "/MUX 3") (class "Default")
      (node (ref "C11") (pin "1") (pinfunction "1_1") (pintype "passive"))
      (node (ref "U14") (pin "1") (pinfunction "COMMON_INPUT/OUTPUT_1") (pintype "bidirectional"))
    )
    (net (code "5") (name "/MUX 4") (class "Default")
      (node (ref "C12") (pin "1") (pinfunction "1_1") (pintype "passive"))
      (node (ref "U15") (pin "1") (pinfunction "COMMON_INPUT/OUTPUT_1") (pintype "bidirectional"))
    )
    (net (code "6") (name "/MUX BANK PWR B") (class "Default")
      (node (ref "R100") (pin "1") (pinfunction "1_1") (pintype "passive"))
      (node (ref "R101") (pin "1") (pinfunction "1_1") (pintype "passive"))
      (node (ref "R102") (pin "1") (pinfunction "1_1") (pintype "passive"))
      (node (ref "R103") (pin "1") (pinfunction "1_1") (pintype "passive"))
      (node (ref "R104") (pin "1") (pinfunction "1_1") (pintype "passive"))
      (node (ref "R105") (pin "1") (pinfunction "1_1") (pintype "passive"))
      (node (ref "R106") (pin "1") (pinfunction "1_1") (pintype "passive"))
      (node (ref "R107") (pin "1") (pinfunction "1_1") (pintype "passive"))
      (node (ref "R108") (pin "1") (pinfunction "1_1") (pintype "passive"))
      (node (ref "R109") (pin "1") (pinfunction "1_1") (pintype "passive"))
      (node (ref "R110") (pin "1") (pinfunction "1_1") (pintype "passive"))
      (node (ref "R111") (pin "1") (pinfunction "1_1") (pintype "passive"))
      (node (ref "R112") (pin "1") (pinfunction "1_1") (pintype "passive"))
      (node (ref "R113") (pin "1") (pinfunction "1_1") (pintype "passive"))
      (node (ref "R114") (pin "1") (pinfunction "1_1") (pintype "passive"))
      (node (ref "R115") (pin "1") (pinfunction "1_1") (pintype "passive"))
      (node (ref "R116") (pin "1") (pinfunction "1_1") (pintype "passive"))
      (node (ref "R117") (pin "1") (pinfunction "1_1") (pintype "passive"))
      (node (ref "R118") (pin "1") (pinfunction "1_1") (pintype "passive"))
      (node (ref "R119") (pin "1") (pinfunction "1_1") (pintype "passive"))
      (node (ref "R120") (pin "1") (pinfunction "1_1") (pintype "passive"))
      (node (ref "R61") (pin "1") (pinfunction "1_1") (pintype "passive"))
      (node (ref "R62") (pin "1") (pinfunction "1_1") (pintype "passive"))
      (node (ref "R63") (pin "1") (pinfunction "1_1") (pintype "passive"))
      (node (ref "R64") (pin "1") (pinfunction "1_1") (pintype "passive"))
      (node (ref "R65") (pin "1") (pinfunction "1_1") (pintype "passive"))
      (node (ref "R66") (pin "1") (pinfunction "1_1") (pintype "passive"))
      (node (ref "R67") (pin "1") (pinfunction "1_1") (pintype "passive"))
      (node (ref "R68") (pin "1") (pinfunction "1_1") (pintype "passive"))
      (node (ref "R69") (pin "1") (pinfunction "1_1") (pintype "passive"))
      (node (ref "R70") (pin "1") (pinfunction "1_1") (pintype "passive"))
      (node (ref "R71") (pin "1") (pinfunction "1_1") (pintype "passive"))
      (node (ref "R72") (pin "1") (pinfunction "1_1") (pintype "passive"))
      (node (ref "R73") (pin "1") (pinfunction "1_1") (pintype "passive"))
      (node (ref "R74") (pin "1") (pinfunction "1_1") (pintype "passive"))
      (node (ref "R75") (pin "1") (pinfunction "1_1") (pintype "passive"))
      (node (ref "R76") (pin "1") (pinfunction "1_1") (pintype "passive"))
      (node (ref "R77") (pin "1") (pinfunction "1_1") (pintype "passive"))
      (node (ref "R78") (pin "1") (pinfunction "1_1") (pintype "passive"))
      (node (ref "R79") (pin "1") (pinfunction "1_1") (pintype "passive"))
      (node (ref "R80") (pin "1") (pinfunction "1_1") (pintype "passive"))
      (node (ref "R81") (pin "1") (pinfunction "1_1") (pintype "passive"))
      (node (ref "R82") (pin "1") (pinfunction "1_1") (pintype "passive"))
      (node (ref "R83") (pin "1") (pinfunction "1_1") (pintype "passive"))
      (node (ref "R84") (pin "1") (pinfunction "1_1") (pintype "passive"))
      (node (ref "R85") (pin "1") (pinfunction "1_1") (pintype "passive"))
      (node (ref "R86") (pin "1") (pinfunction "1_1") (pintype "passive"))
      (node (ref "R87") (pin "1") (pinfunction "1_1") (pintype "passive"))
      (node (ref "R88") (pin "1") (pinfunction "1_1") (pintype "passive"))
      (node (ref "R89") (pin "1") (pinfunction "1_1") (pintype "passive"))
      (node (ref "R90") (pin "1") (pinfunction "1_1") (pintype "passive"))
      (node (ref "R91") (pin "1") (pinfunction "1_1") (pintype "passive"))
      (node (ref "R92") (pin "1") (pinfunction "1_1") (pintype "passive"))
      (node (ref "R93") (pin "1") (pinfunction "1_1") (pintype "passive"))
      (node (ref "R94") (pin "1") (pinfunction "1_1") (pintype "passive"))
      (node (ref "R95") (pin "1") (pinfunction "1_1") (pintype "passive"))
      (node (ref "R96") (pin "1") (pinfunction "1_1") (pintype "passive"))
      (node (ref "R97") (pin "1") (pinfunction "1_1") (pintype "passive"))
      (node (ref "R98") (pin "1") (pinfunction "1_1") (pintype "passive"))
      (node (ref "R99") (pin "1") (pinfunction "1_1") (pintype "passive"))
      (node (ref "U11") (pin "24") (pinfunction "VCC_24") (pintype "power_in"))
      (node (ref "U12") (pin "24") (pinfunction "VCC_24") (pintype "power_in"))
      (node (ref "U13") (pin "24") (pinfunction "VCC_24") (pintype "power_in"))
      (node (ref "U14") (pin "24") (pinfunction "VCC_24") (pintype "power_in"))
      (node (ref "U15") (pin "24") (pinfunction "VCC_24") (pintype "power_in"))
    )
    (net (code "7") (name "/S0") (class "Default")
      (node (ref "U11") (pin "10") (pinfunction "S0_10") (pintype "input"))
      (node (ref "U12") (pin "10") (pinfunction "S0_10") (pintype "input"))
      (node (ref "U13") (pin "10") (pinfunction "S0_10") (pintype "input"))
      (node (ref "U14") (pin "10") (pinfunction "S0_10") (pintype "input"))
      (node (ref "U15") (pin "10") (pinfunction "S0_10") (pintype "input"))
    )
    (net (code "8") (name "/S1") (class "Default")
      (node (ref "U11") (pin "11") (pinfunction "S1_11") (pintype "input"))
      (node (ref "U12") (pin "11") (pinfunction "S1_11") (pintype "input"))
      (node (ref "U13") (pin "11") (pinfunction "S1_11") (pintype "input"))
      (node (ref "U14") (pin "11") (pinfunction "S1_11") (pintype "input"))
      (node (ref "U15") (pin "11") (pinfunction "S1_11") (pintype "input"))
    )
    (net (code "9") (name "/S2") (class "Default")
      (node (ref "U11") (pin "14") (pinfunction "S2_14") (pintype "input"))
      (node (ref "U12") (pin "14") (pinfunction "S2_14") (pintype "input"))
      (node (ref "U13") (pin "14") (pinfunction "S2_14") (pintype "input"))
      (node (ref "U14") (pin "14") (pinfunction "S2_14") (pintype "input"))
      (node (ref "U15") (pin "14") (pinfunction "S2_14") (pintype "input"))
    )
    (net (code "10") (name "/S3") (class "Default")
      (node (ref "U11") (pin "13") (pinfunction "S3_13") (pintype "input"))
      (node (ref "U12") (pin "13") (pinfunction "S3_13") (pintype "input"))
      (node (ref "U13") (pin "13") (pinfunction "S3_13") (pintype "input"))
      (node (ref "U14") (pin "13") (pinfunction "S3_13") (pintype "input"))
      (node (ref "U15") (pin "13") (pinfunction "S3_13") (pintype "input"))
    )
    (net (code "11") (name "GND") (class "Default")
      (node (ref "C10") (pin "2") (pinfunction "2_2") (pintype "passive"))
      (node (ref "C11") (pin "2") (pinfunction "2_2") (pintype "passive"))
      (node (ref "C12") (pin "2") (pinfunction "2_2") (pintype "passive"))
      (node (ref "C8") (pin "2") (pinfunction "2_2") (pintype "passive"))
      (node (ref "C9") (pin "2") (pinfunction "2_2") (pintype "passive"))
      (node (ref "J10") (pin "10") (pinfunction "10_10") (pintype "passive"))
      (node (ref "J10") (pin "12") (pinfunction "12_12") (pintype "passive"))
      (node (ref "J10") (pin "14") (pinfunction "14_14") (pintype "passive"))
      (node (ref "J10") (pin "16") (pinfunction "16_16") (pintype "passive"))
      (node (ref "J10") (pin "18") (pinfunction "18_18") (pintype "passive"))
      (node (ref "J10") (pin "2") (pinfunction "2_2") (pintype "passive"))
      (node (ref "J10") (pin "20") (pinfunction "20_20") (pintype "passive"))
      (node (ref "J10") (pin "22") (pinfunction "22_22") (pintype "passive"))
      (node (ref "J10") (pin "24") (pinfunction "24_24") (pintype "passive"))
      (node (ref "J10") (pin "4") (pinfunction "4_4") (pintype "passive"))
      (node (ref "J10") (pin "6") (pinfunction "6_6") (pintype "passive"))
      (node (ref "J10") (pin "8") (pinfunction "8_8") (pintype "passive"))
      (node (ref "J11") (pin "10") (pinfunction "10_10") (pintype "passive"))
      (node (ref "J11") (pin "12") (pinfunction "12_12") (pintype "passive"))
      (node (ref "J11") (pin "14") (pinfunction "14_14") (pintype "passive"))
      (node (ref "J11") (pin "16") (pinfunction "16_16") (pintype "passive"))
      (node (ref "J11") (pin "18") (pinfunction "18_18") (pintype "passive"))
      (node (ref "J11") (pin "2") (pinfunction "2_2") (pintype "passive"))
      (node (ref "J11") (pin "20") (pinfunction "20_20") (pintype "passive"))
      (node (ref "J11") (pin "22") (pinfunction "22_22") (pintype "passive"))
      (node (ref "J11") (pin "24") (pinfunction "24_24") (pintype "passive"))
      (node (ref "J11") (pin "4") (pinfunction "4_4") (pintype "passive"))
      (node (ref "J11") (pin "6") (pinfunction "6_6") (pintype "passive"))
      (node (ref "J11") (pin "8") (pinfunction "8_8") (pintype "passive"))
      (node (ref "J7") (pin "10") (pinfunction "10_10") (pintype "passive"))
      (node (ref "J7") (pin "12") (pinfunction "12_12") (pintype "passive"))
      (node (ref "J7") (pin "14") (pinfunction "14_14") (pintype "passive"))
      (node (ref "J7") (pin "16") (pinfunction "16_16") (pintype "passive"))
      (node (ref "J7") (pin "18") (pinfunction "18_18") (pintype "passive"))
      (node (ref "J7") (pin "2") (pinfunction "2_2") (pintype "passive"))
      (node (ref "J7") (pin "20") (pinfunction "20_20") (pintype "passive"))
      (node (ref "J7") (pin "22") (pinfunction "22_22") (pintype "passive"))
      (node (ref "J7") (pin "24") (pinfunction "24_24") (pintype "passive"))
      (node (ref "J7") (pin "4") (pinfunction "4_4") (pintype "passive"))
      (node (ref "J7") (pin "6") (pinfunction "6_6") (pintype "passive"))
      (node (ref "J7") (pin "8") (pinfunction "8_8") (pintype "passive"))
      (node (ref "J8") (pin "10") (pinfunction "10_10") (pintype "passive"))
      (node (ref "J8") (pin "12") (pinfunction "12_12") (pintype "passive"))
      (node (ref "J8") (pin "14") (pinfunction "14_14") (pintype "passive"))
      (node (ref "J8") (pin "16") (pinfunction "16_16") (pintype "passive"))
      (node (ref "J8") (pin "18") (pinfunction "18_18") (pintype "passive"))
      (node (ref "J8") (pin "2") (pinfunction "2_2") (pintype "passive"))
      (node (ref "J8") (pin "20") (pinfunction "20_20") (pintype "passive"))
      (node (ref "J8") (pin "22") (pinfunction "22_22") (pintype "passive"))
      (node (ref "J8") (pin "24") (pinfunction "24_24") (pintype "passive"))
      (node (ref "J8") (pin "4") (pinfunction "4_4") (pintype "passive"))
      (node (ref "J8") (pin "6") (pinfunction "6_6") (pintype "passive"))
      (node (ref "J8") (pin "8") (pinfunction "8_8") (pintype "passive"))
      (node (ref "J9") (pin "10") (pinfunction "10_10") (pintype "passive"))
      (node (ref "J9") (pin "12") (pinfunction "12_12") (pintype "passive"))
      (node (ref "J9") (pin "14") (pinfunction "14_14") (pintype "passive"))
      (node (ref "J9") (pin "16") (pinfunction "16_16") (pintype "passive"))
      (node (ref "J9") (pin "18") (pinfunction "18_18") (pintype "passive"))
      (node (ref "J9") (pin "2") (pinfunction "2_2") (pintype "passive"))
      (node (ref "J9") (pin "20") (pinfunction "20_20") (pintype "passive"))
      (node (ref "J9") (pin "22") (pinfunction "22_22") (pintype "passive"))
      (node (ref "J9") (pin "24") (pinfunction "24_24") (pintype "passive"))
      (node (ref "J9") (pin "4") (pinfunction "4_4") (pintype "passive"))
      (node (ref "J9") (pin "6") (pinfunction "6_6") (pintype "passive"))
      (node (ref "J9") (pin "8") (pinfunction "8_8") (pintype "passive"))
      (node (ref "U11") (pin "12") (pinfunction "GND_12") (pintype "power_in"))
      (node (ref "U11") (pin "15") (pinfunction "~{E}_15") (pintype "input"))
      (node (ref "U12") (pin "12") (pinfunction "GND_12") (pintype "power_in"))
      (node (ref "U12") (pin "15") (pinfunction "~{E}_15") (pintype "input"))
      (node (ref "U13") (pin "12") (pinfunction "GND_12") (pintype "power_in"))
      (node (ref "U13") (pin "15") (pinfunction "~{E}_15") (pintype "input"))
      (node (ref "U14") (pin "12") (pinfunction "GND_12") (pintype "power_in"))
      (node (ref "U14") (pin "15") (pinfunction "~{E}_15") (pintype "input"))
      (node (ref "U15") (pin "12") (pinfunction "GND_12") (pintype "power_in"))
      (node (ref "U15") (pin "15") (pinfunction "~{E}_15") (pintype "input"))
    )
    (net (code "12") (name "Net-(U11-I0)") (class "Default")
      (node (ref "J7") (pin "1") (pinfunction "1_1") (pintype "passive"))
      (node (ref "R61") (pin "2") (pinfunction "2_2") (pintype "passive"))
      (node (ref "U11") (pin "9") (pinfunction "I0_9") (pintype "input"))
    )
    (net (code "13") (name "Net-(U11-I1)") (class "Default")
      (node (ref "J7") (pin "3") (pinfunction "3_3") (pintype "passive"))
      (node (ref "R62") (pin "2") (pinfunction "2_2") (pintype "passive"))
      (node (ref "U11") (pin "8") (pinfunction "I1_8") (pintype "input"))
    )
    (net (code "14") (name "Net-(U11-I2)") (class "Default")
      (node (ref "J7") (pin "5") (pinfunction "5_5") (pintype "passive"))
      (node (ref "R63") (pin "2") (pinfunction "2_2") (pintype "passive"))
      (node (ref "U11") (pin "7") (pinfunction "I2_7") (pintype "input"))
    )
    (net (code "15") (name "Net-(U11-I3)") (class "Default")
      (node (ref "J7") (pin "7") (pinfunction "7_7") (pintype "passive"))
      (node (ref "R64") (pin "2") (pinfunction "2_2") (pintype "passive"))
      (node (ref "U11") (pin "6") (pinfunction "I3_6") (pintype "input"))
    )
    (net (code "16") (name "Net-(U11-I4)") (class "Default")
      (node (ref "J7") (pin "9") (pinfunction "9_9") (pintype "passive"))
      (node (ref "R65") (pin "2") (pinfunction "2_2") (pintype "passive"))
      (node (ref "U11") (pin "5") (pinfunction "I4_5") (pintype "input"))
    )
    (net (code "17") (name "Net-(U11-I5)") (class "Default")
      (node (ref "J7") (pin "11") (pinfunction "11_11") (pintype "passive"))
      (node (ref "R66") (pin "2") (pinfunction "2_2") (pintype "passive"))
      (node (ref "U11") (pin "4") (pinfunction "I5_4") (pintype "input"))
    )
    (net (code "18") (name "Net-(U11-I6)") (class "Default")
      (node (ref "J7") (pin "13") (pinfunction "13_13") (pintype "passive"))
      (node (ref "R67") (pin "2") (pinfunction "2_2") (pintype "passive"))
      (node (ref "U11") (pin "3") (pinfunction "I6_3") (pintype "input"))
    )
    (net (code "19") (name "Net-(U11-I7)") (class "Default")
      (node (ref "J7") (pin "15") (pinfunction "15_15") (pintype "passive"))
      (node (ref "R68") (pin "2") (pinfunction "2_2") (pintype "passive"))
      (node (ref "U11") (pin "2") (pinfunction "I7_2") (pintype "input"))
    )
    (net (code "20") (name "Net-(U11-I8)") (class "Default")
      (node (ref "J7") (pin "17") (pinfunction "17_17") (pintype "passive"))
      (node (ref "R69") (pin "2") (pinfunction "2_2") (pintype "passive"))
      (node (ref "U11") (pin "23") (pinfunction "I8_23") (pintype "input"))
    )
    (net (code "21") (name "Net-(U11-I9)") (class "Default")
      (node (ref "J7") (pin "19") (pinfunction "19_19") (pintype "passive"))
      (node (ref "R70") (pin "2") (pinfunction "2_2") (pintype "passive"))
      (node (ref "U11") (pin "22") (pinfunction "I9_22") (pintype "input"))
    )
    (net (code "22") (name "Net-(U11-I10)") (class "Default")
      (node (ref "J7") (pin "21") (pinfunction "21_21") (pintype "passive"))
      (node (ref "R71") (pin "2") (pinfunction "2_2") (pintype "passive"))
      (node (ref "U11") (pin "21") (pinfunction "I10_21") (pintype "input"))
    )
    (net (code "23") (name "Net-(U11-I11)") (class "Default")
      (node (ref "J7") (pin "23") (pinfunction "23_23") (pintype "passive"))
      (node (ref "R72") (pin "2") (pinfunction "2_2") (pintype "passive"))
      (node (ref "U11") (pin "20") (pinfunction "I11_20") (pintype "input"))
    )
    (net (code "24") (name "Net-(U12-I0)") (class "Default")
      (node (ref "J8") (pin "1") (pinfunction "1_1") (pintype "passive"))
      (node (ref "R73") (pin "2") (pinfunction "2_2") (pintype "passive"))
      (node (ref "U12") (pin "9") (pinfunction "I0_9") (pintype "input"))
    )
    (net (code "25") (name "Net-(U12-I1)") (class "Default")
      (node (ref "J8") (pin "3") (pinfunction "3_3") (pintype "passive"))
      (node (ref "R74") (pin "2") (pinfunction "2_2") (pintype "passive"))
      (node (ref "U12") (pin "8") (pinfunction "I1_8") (pintype "input"))
    )
    (net (code "26") (name "Net-(U12-I2)") (class "Default")
      (node (ref "J8") (pin "5") (pinfunction "5_5") (pintype "passive"))
      (node (ref "R75") (pin "2") (pinfunction "2_2") (pintype "passive"))
      (node (ref "U12") (pin "7") (pinfunction "I2_7") (pintype "input"))
    )
    (net (code "27") (name "Net-(U12-I3)") (class "Default")
      (node (ref "J8") (pin "7") (pinfunction "7_7") (pintype "passive"))
      (node (ref "R76") (pin "2") (pinfunction "2_2") (pintype "passive"))
      (node (ref "U12") (pin "6") (pinfunction "I3_6") (pintype "input"))
    )
    (net (code "28") (name "Net-(U12-I4)") (class "Default")
      (node (ref "J8") (pin "9") (pinfunction "9_9") (pintype "passive"))
      (node (ref "R77") (pin "2") (pinfunction "2_2") (pintype "passive"))
      (node (ref "U12") (pin "5") (pinfunction "I4_5") (pintype "input"))
    )
    (net (code "29") (name "Net-(U12-I5)") (class "Default")
      (node (ref "J8") (pin "11") (pinfunction "11_11") (pintype "passive"))
      (node (ref "R78") (pin "2") (pinfunction "2_2") (pintype "passive"))
      (node (ref "U12") (pin "4") (pinfunction "I5_4") (pintype "input"))
    )
    (net (code "30") (name "Net-(U12-I6)") (class "Default")
      (node (ref "J8") (pin "13") (pinfunction "13_13") (pintype "passive"))
      (node (ref "R79") (pin "2") (pinfunction "2_2") (pintype "passive"))
      (node (ref "U12") (pin "3") (pinfunction "I6_3") (pintype "input"))
    )
    (net (code "31") (name "Net-(U12-I7)") (class "Default")
      (node (ref "J8") (pin "15") (pinfunction "15_15") (pintype "passive"))
      (node (ref "R80") (pin "2") (pinfunction "2_2") (pintype "passive"))
      (node (ref "U12") (pin "2") (pinfunction "I7_2") (pintype "input"))
    )
    (net (code "32") (name "Net-(U12-I8)") (class "Default")
      (node (ref "J8") (pin "17") (pinfunction "17_17") (pintype "passive"))
      (node (ref "R81") (pin "2") (pinfunction "2_2") (pintype "passive"))
      (node (ref "U12") (pin "23") (pinfunction "I8_23") (pintype "input"))
    )
    (net (code "33") (name "Net-(U12-I9)") (class "Default")
      (node (ref "J8") (pin "19") (pinfunction "19_19") (pintype "passive"))
      (node (ref "R82") (pin "2") (pinfunction "2_2") (pintype "passive"))
      (node (ref "U12") (pin "22") (pinfunction "I9_22") (pintype "input"))
    )
    (net (code "34") (name "Net-(U12-I10)") (class "Default")
      (node (ref "J8") (pin "21") (pinfunction "21_21") (pintype "passive"))
      (node (ref "R83") (pin "2") (pinfunction "2_2") (pintype "passive"))
      (node (ref "U12") (pin "21") (pinfunction "I10_21") (pintype "input"))
    )
    (net (code "35") (name "Net-(U12-I11)") (class "Default")
      (node (ref "J8") (pin "23") (pinfunction "23_23") (pintype "passive"))
      (node (ref "R84") (pin "2") (pinfunction "2_2") (pintype "passive"))
      (node (ref "U12") (pin "20") (pinfunction "I11_20") (pintype "input"))
    )
    (net (code "36") (name "Net-(U13-I0)") (class "Default")
      (node (ref "J9") (pin "1") (pinfunction "1_1") (pintype "passive"))
      (node (ref "R85") (pin "2") (pinfunction "2_2") (pintype "passive"))
      (node (ref "U13") (pin "9") (pinfunction "I0_9") (pintype "input"))
    )
    (net (code "37") (name "Net-(U13-I1)") (class "Default")
      (node (ref "J9") (pin "3") (pinfunction "3_3") (pintype "passive"))
      (node (ref "R86") (pin "2") (pinfunction "2_2") (pintype "passive"))
      (node (ref "U13") (pin "8") (pinfunction "I1_8") (pintype "input"))
    )
    (net (code "38") (name "Net-(U13-I2)") (class "Default")
      (node (ref "J9") (pin "5") (pinfunction "5_5") (pintype "passive"))
      (node (ref "R87") (pin "2") (pinfunction "2_2") (pintype "passive"))
      (node (ref "U13") (pin "7") (pinfunction "I2_7") (pintype "input"))
    )
    (net (code "39") (name "Net-(U13-I3)") (class "Default")
      (node (ref "J9") (pin "7") (pinfunction "7_7") (pintype "passive"))
      (node (ref "R88") (pin "2") (pinfunction "2_2") (pintype "passive"))
      (node (ref "U13") (pin "6") (pinfunction "I3_6") (pintype "input"))
    )
    (net (code "40") (name "Net-(U13-I4)") (class "Default")
      (node (ref "J9") (pin "9") (pinfunction "9_9") (pintype "passive"))
      (node (ref "R89") (pin "2") (pinfunction "2_2") (pintype "passive"))
      (node (ref "U13") (pin "5") (pinfunction "I4_5") (pintype "input"))
    )
    (net (code "41") (name "Net-(U13-I5)") (class "Default")
      (node (ref "J9") (pin "11") (pinfunction "11_11") (pintype "passive"))
      (node (ref "R90") (pin "2") (pinfunction "2_2") (pintype "passive"))
      (node (ref "U13") (pin "4") (pinfunction "I5_4") (pintype "input"))
    )
    (net (code "42") (name "Net-(U13-I6)") (class "Default")
      (node (ref "J9") (pin "13") (pinfunction "13_13") (pintype "passive"))
      (node (ref "R91") (pin "2") (pinfunction "2_2") (pintype "passive"))
      (node (ref "U13") (pin "3") (pinfunction "I6_3") (pintype "input"))
    )
    (net (code "43") (name "Net-(U13-I7)") (class "Default")
      (node (ref "J9") (pin "15") (pinfunction "15_15") (pintype "passive"))
      (node (ref "R92") (pin "2") (pinfunction "2_2") (pintype "passive"))
      (node (ref "U13") (pin "2") (pinfunction "I7_2") (pintype "input"))
    )
    (net (code "44") (name "Net-(U13-I8)") (class "Default")
      (node (ref "J9") (pin "17") (pinfunction "17_17") (pintype "passive"))
      (node (ref "R93") (pin "2") (pinfunction "2_2") (pintype "passive"))
      (node (ref "U13") (pin "23") (pinfunction "I8_23") (pintype "input"))
    )
    (net (code "45") (name "Net-(U13-I9)") (class "Default")
      (node (ref "J9") (pin "19") (pinfunction "19_19") (pintype "passive"))
      (node (ref "R94") (pin "2") (pinfunction "2_2") (pintype "passive"))
      (node (ref "U13") (pin "22") (pinfunction "I9_22") (pintype "input"))
    )
    (net (code "46") (name "Net-(U13-I10)") (class "Default")
      (node (ref "J9") (pin "21") (pinfunction "21_21") (pintype "passive"))
      (node (ref "R95") (pin "2") (pinfunction "2_2") (pintype "passive"))
      (node (ref "U13") (pin "21") (pinfunction "I10_21") (pintype "input"))
    )
    (net (code "47") (name "Net-(U13-I11)") (class "Default")
      (node (ref "J9") (pin "23") (pinfunction "23_23") (pintype "passive"))
      (node (ref "R96") (pin "2") (pinfunction "2_2") (pintype "passive"))
      (node (ref "U13") (pin "20") (pinfunction "I11_20") (pintype "input"))
    )
    (net (code "48") (name "Net-(U14-I0)") (class "Default")
      (node (ref "J10") (pin "1") (pinfunction "1_1") (pintype "passive"))
      (node (ref "R97") (pin "2") (pinfunction "2_2") (pintype "passive"))
      (node (ref "U14") (pin "9") (pinfunction "I0_9") (pintype "input"))
    )
    (net (code "49") (name "Net-(U14-I1)") (class "Default")
      (node (ref "J10") (pin "3") (pinfunction "3_3") (pintype "passive"))
      (node (ref "R98") (pin "2") (pinfunction "2_2") (pintype "passive"))
      (node (ref "U14") (pin "8") (pinfunction "I1_8") (pintype "input"))
    )
    (net (code "50") (name "Net-(U14-I2)") (class "Default")
      (node (ref "J10") (pin "5") (pinfunction "5_5") (pintype "passive"))
      (node (ref "R99") (pin "2") (pinfunction "2_2") (pintype "passive"))
      (node (ref "U14") (pin "7") (pinfunction "I2_7") (pintype "input"))
    )
    (net (code "51") (name "Net-(U14-I3)") (class "Default")
      (node (ref "J10") (pin "7") (pinfunction "7_7") (pintype "passive"))
      (node (ref "R100") (pin "2") (pinfunction "2_2") (pintype "passive"))
      (node (ref "U14") (pin "6") (pinfunction "I3_6") (pintype "input"))
    )
    (net (code "52") (name "Net-(U14-I4)") (class "Default")
      (node (ref "J10") (pin "9") (pinfunction "9_9") (pintype "passive"))
      (node (ref "R101") (pin "2") (pinfunction "2_2") (pintype "passive"))
      (node (ref "U14") (pin "5") (pinfunction "I4_5") (pintype "input"))
    )
    (net (code "53") (name "Net-(U14-I5)") (class "Default")
      (node (ref "J10") (pin "11") (pinfunction "11_11") (pintype "passive"))
      (node (ref "R102") (pin "2") (pinfunction "2_2") (pintype "passive"))
      (node (ref "U14") (pin "4") (pinfunction "I5_4") (pintype "input"))
    )
    (net (code "54") (name "Net-(U14-I6)") (class "Default")
      (node (ref "J10") (pin "13") (pinfunction "13_13") (pintype "passive"))
      (node (ref "R103") (pin "2") (pinfunction "2_2") (pintype "passive"))
      (node (ref "U14") (pin "3") (pinfunction "I6_3") (pintype "input"))
    )
    (net (code "55") (name "Net-(U14-I7)") (class "Default")
      (node (ref "J10") (pin "15") (pinfunction "15_15") (pintype "passive"))
      (node (ref "R104") (pin "2") (pinfunction "2_2") (pintype "passive"))
      (node (ref "U14") (pin "2") (pinfunction "I7_2") (pintype "input"))
    )
    (net (code "56") (name "Net-(U14-I8)") (class "Default")
      (node (ref "J10") (pin "17") (pinfunction "17_17") (pintype "passive"))
      (node (ref "R105") (pin "2") (pinfunction "2_2") (pintype "passive"))
      (node (ref "U14") (pin "23") (pinfunction "I8_23") (pintype "input"))
    )
    (net (code "57") (name "Net-(U14-I9)") (class "Default")
      (node (ref "J10") (pin "19") (pinfunction "19_19") (pintype "passive"))
      (node (ref "R106") (pin "2") (pinfunction "2_2") (pintype "passive"))
      (node (ref "U14") (pin "22") (pinfunction "I9_22") (pintype "input"))
    )
    (net (code "58") (name "Net-(U14-I10)") (class "Default")
      (node (ref "J10") (pin "21") (pinfunction "21_21") (pintype "passive"))
      (node (ref "R107") (pin "2") (pinfunction "2_2") (pintype "passive"))
      (node (ref "U14") (pin "21") (pinfunction "I10_21") (pintype "input"))
    )
    (net (code "59") (name "Net-(U14-I11)") (class "Default")
      (node (ref "J10") (pin "23") (pinfunction "23_23") (pintype "passive"))
      (node (ref "R108") (pin "2") (pinfunction "2_2") (pintype "passive"))
      (node (ref "U14") (pin "20") (pinfunction "I11_20") (pintype "input"))
    )
    (net (code "60") (name "Net-(U15-I0)") (class "Default")
      (node (ref "J11") (pin "1") (pinfunction "1_1") (pintype "passive"))
      (node (ref "R109") (pin "2") (pinfunction "2_2") (pintype "passive"))
      (node (ref "U15") (pin "9") (pinfunction "I0_9") (pintype "input"))
    )
    (net (code "61") (name "Net-(U15-I1)") (class "Default")
      (node (ref "J11") (pin "3") (pinfunction "3_3") (pintype "passive"))
      (node (ref "R110") (pin "2") (pinfunction "2_2") (pintype "passive"))
      (node (ref "U15") (pin "8") (pinfunction "I1_8") (pintype "input"))
    )
    (net (code "62") (name "Net-(U15-I2)") (class "Default")
      (node (ref "J11") (pin "5") (pinfunction "5_5") (pintype "passive"))
      (node (ref "R111") (pin "2") (pinfunction "2_2") (pintype "passive"))
      (node (ref "U15") (pin "7") (pinfunction "I2_7") (pintype "input"))
    )
    (net (code "63") (name "Net-(U15-I3)") (class "Default")
      (node (ref "J11") (pin "7") (pinfunction "7_7") (pintype "passive"))
      (node (ref "R112") (pin "2") (pinfunction "2_2") (pintype "passive"))
      (node (ref "U15") (pin "6") (pinfunction "I3_6") (pintype "input"))
    )
    (net (code "64") (name "Net-(U15-I4)") (class "Default")
      (node (ref "J11") (pin "9") (pinfunction "9_9") (pintype "passive"))
      (node (ref "R113") (pin "2") (pinfunction "2_2") (pintype "passive"))
      (node (ref "U15") (pin "5") (pinfunction "I4_5") (pintype "input"))
    )
    (net (code "65") (name "Net-(U15-I5)") (class "Default")
      (node (ref "J11") (pin "11") (pinfunction "11_11") (pintype "passive"))
      (node (ref "R114") (pin "2") (pinfunction "2_2") (pintype "passive"))
      (node (ref "U15") (pin "4") (pinfunction "I5_4") (pintype "input"))
    )
    (net (code "66") (name "Net-(U15-I6)") (class "Default")
      (node (ref "J11") (pin "13") (pinfunction "13_13") (pintype "passive"))
      (node (ref "R115") (pin "2") (pinfunction "2_2") (pintype "passive"))
      (node (ref "U15") (pin "3") (pinfunction "I6_3") (pintype "input"))
    )
    (net (code "67") (name "Net-(U15-I7)") (class "Default")
      (node (ref "J11") (pin "15") (pinfunction "15_15") (pintype "passive"))
      (node (ref "R116") (pin "2") (pinfunction "2_2") (pintype "passive"))
      (node (ref "U15") (pin "2") (pinfunction "I7_2") (pintype "input"))
    )
    (net (code "68") (name "Net-(U15-I8)") (class "Default")
      (node (ref "J11") (pin "17") (pinfunction "17_17") (pintype "passive"))
      (node (ref "R117") (pin "2") (pinfunction "2_2") (pintype "passive"))
      (node (ref "U15") (pin "23") (pinfunction "I8_23") (pintype "input"))
    )
    (net (code "69") (name "Net-(U15-I9)") (class "Default")
      (node (ref "J11") (pin "19") (pinfunction "19_19") (pintype "passive"))
      (node (ref "R118") (pin "2") (pinfunction "2_2") (pintype "passive"))
      (node (ref "U15") (pin "22") (pinfunction "I9_22") (pintype "input"))
    )
    (net (code "70") (name "Net-(U15-I10)") (class "Default")
      (node (ref "J11") (pin "21") (pinfunction "21_21") (pintype "passive"))
      (node (ref "R119") (pin "2") (pinfunction "2_2") (pintype "passive"))
      (node (ref "U15") (pin "21") (pinfunction "I10_21") (pintype "input"))
    )
    (net (code "71") (name "Net-(U15-I11)") (class "Default")
      (node (ref "J11") (pin "23") (pinfunction "23_23") (pintype "passive"))
      (node (ref "R120") (pin "2") (pinfunction "2_2") (pintype "passive"))
      (node (ref "U15") (pin "20") (pinfunction "I11_20") (pintype "input"))
    )
    (net (code "72") (name "unconnected-(U11-I12-Pad19)") (class "Default")
      (node (ref "U11") (pin "19") (pinfunction "I12_19") (pintype "input+no_connect"))
    )
    (net (code "73") (name "unconnected-(U11-I13-Pad18)") (class "Default")
      (node (ref "U11") (pin "18") (pinfunction "I13_18") (pintype "input+no_connect"))
    )
    (net (code "74") (name "unconnected-(U11-I14-Pad17)") (class "Default")
      (node (ref "U11") (pin "17") (pinfunction "I14_17") (pintype "input+no_connect"))
    )
    (net (code "75") (name "unconnected-(U11-I15-Pad16)") (class "Default")
      (node (ref "U11") (pin "16") (pinfunction "I15_16") (pintype "input+no_connect"))
    )
    (net (code "76") (name "unconnected-(U12-I12-Pad19)") (class "Default")
      (node (ref "U12") (pin "19") (pinfunction "I12_19") (pintype "input+no_connect"))
    )
    (net (code "77") (name "unconnected-(U12-I13-Pad18)") (class "Default")
      (node (ref "U12") (pin "18") (pinfunction "I13_18") (pintype "input+no_connect"))
    )
    (net (code "78") (name "unconnected-(U12-I14-Pad17)") (class "Default")
      (node (ref "U12") (pin "17") (pinfunction "I14_17") (pintype "input+no_connect"))
    )
    (net (code "79") (name "unconnected-(U12-I15-Pad16)") (class "Default")
      (node (ref "U12") (pin "16") (pinfunction "I15_16") (pintype "input+no_connect"))
    )
    (net (code "80") (name "unconnected-(U13-I12-Pad19)") (class "Default")
      (node (ref "U13") (pin "19") (pinfunction "I12_19") (pintype "input+no_connect"))
    )
    (net (code "81") (name "unconnected-(U13-I13-Pad18)") (class "Default")
      (node (ref "U13") (pin "18") (pinfunction "I13_18") (pintype "input+no_connect"))
    )
    (net (code "82") (name "unconnected-(U13-I14-Pad17)") (class "Default")
      (node (ref "U13") (pin "17") (pinfunction "I14_17") (pintype "input+no_connect"))
    )
    (net (code "83") (name "unconnected-(U13-I15-Pad16)") (class "Default")
      (node (ref "U13") (pin "16") (pinfunction "I15_16") (pintype "input+no_connect"))
    )
    (net (code "84") (name "unconnected-(U14-I12-Pad19)") (class "Default")
      (node (ref "U14") (pin "19") (pinfunction "I12_19") (pintype "input+no_connect"))
    )
    (net (code "85") (name "unconnected-(U14-I13-Pad18)") (class "Default")
      (node (ref "U14") (pin "18") (pinfunction "I13_18") (pintype "input+no_connect"))
    )
    (net (code "86") (name "unconnected-(U14-I14-Pad17)") (class "Default")
      (node (ref "U14") (pin "17") (pinfunction "I14_17") (pintype "input+no_connect"))
    )
    (net (code "87") (name "unconnected-(U14-I15-Pad16)") (class "Default")
      (node (ref "U14") (pin "16") (pinfunction "I15_16") (pintype "input+no_connect"))
    )
    (net (code "88") (name "unconnected-(U15-I12-Pad19)") (class "Default")
      (node (ref "U15") (pin "19") (pinfunction "I12_19") (pintype "input+no_connect"))
    )
    (net (code "89") (name "unconnected-(U15-I13-Pad18)") (class "Default")
      (node (ref "U15") (pin "18") (pinfunction "I13_18") (pintype "input+no_connect"))
    )
    (net (code "90") (name "unconnected-(U15-I14-Pad17)") (class "Default")
      (node (ref "U15") (pin "17") (pinfunction "I14_17") (pintype "input+no_connect"))
    )
    (net (code "91") (name "unconnected-(U15-I15-Pad16)") (class "Default")
      (node (ref "U15") (pin "16") (pinfunction "I15_16") (pintype "input+no_connect"))
    )
  )
)
